# STM32G473QETx_LQFP128_MCU.net
KiCad netlist of a schematic drawn in Altium Designer
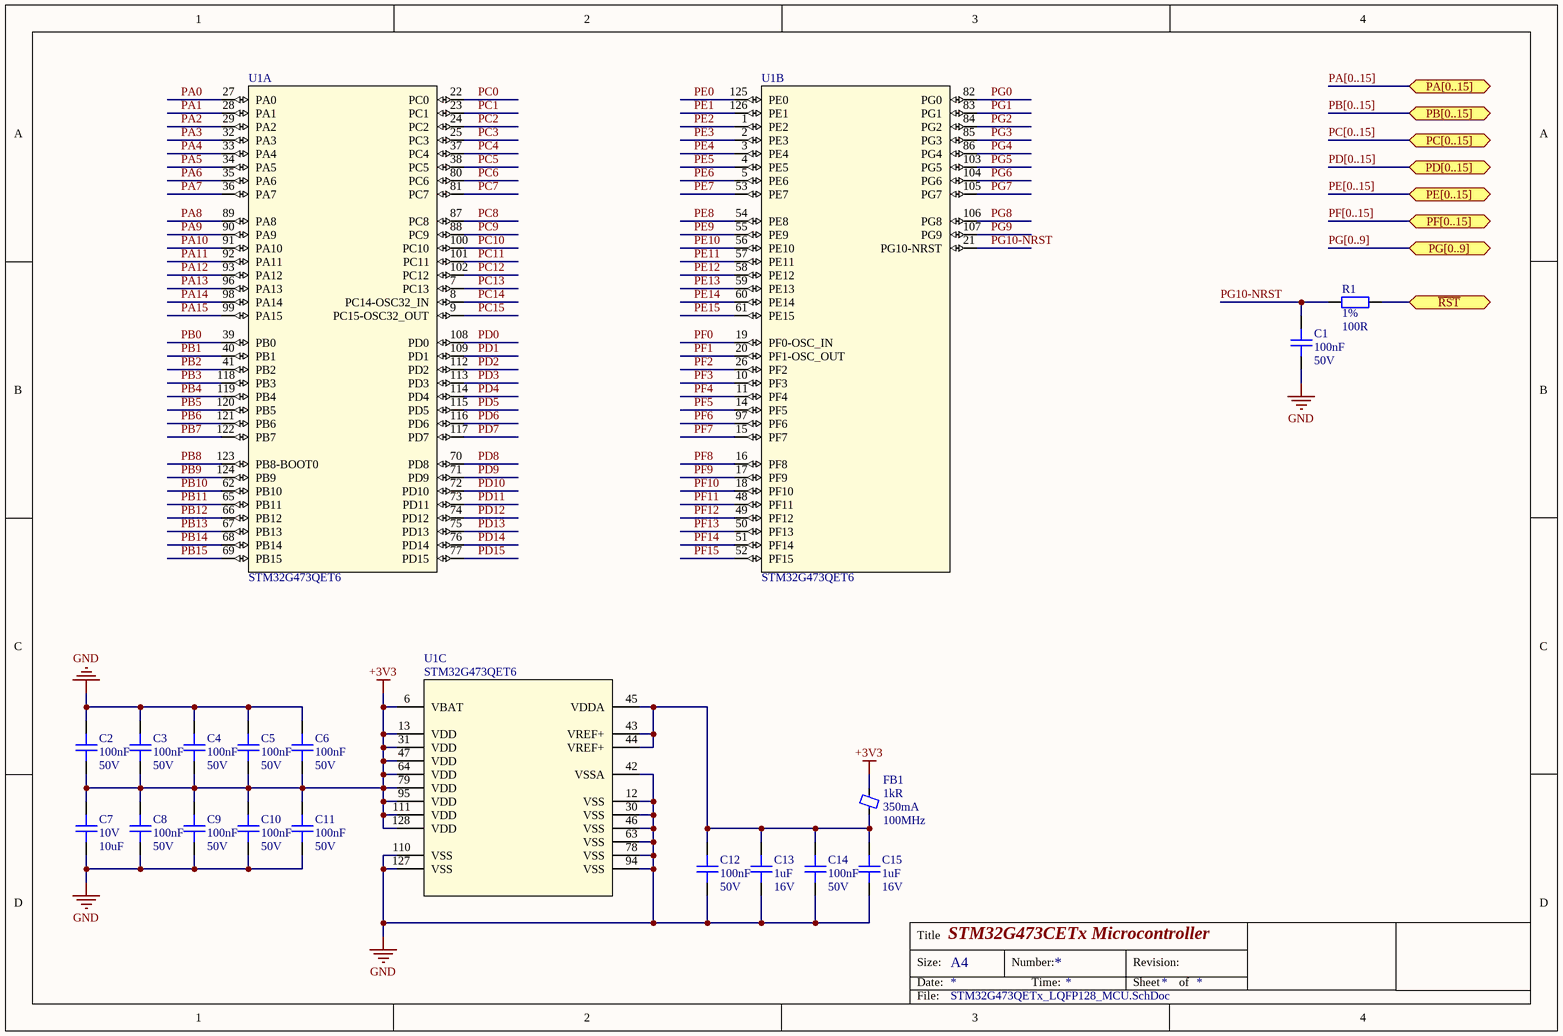
[diagram p0: STM32G473QETx_LQFP128_MCU.SchDoc]

(export (version "E")
  (design (tool "Eeschema 10.0.6"))
  (components
    (comp (ref "C1")
      (value "CAP CER 0.1UF 50V X7R 0402")
      (footprint "C0402")
      (description "0.1µF ±10% 50V Ceramic Capacitor X7R 0402 (1005 Metric)")
      (fields
        (field (name "MANUFACTURER") "TDK")
        (field (name "MANUFACTURER PART NUMBER") "CGA2B3X7R1H104K050BB")
        (field (name "CAPACITANCE") "100nF")
        (field (name "VOLTAGE") "50V")
      )
      (libsource (lib "capacitors_smd") (part "CAP CER 0.1UF 50V X7R 0402"))
    )
    (comp (ref "C2")
      (value "CAP CER 0.1UF 50V X7R 0402")
      (footprint "C0402")
      (description "0.1µF ±10% 50V Ceramic Capacitor X7R 0402 (1005 Metric)")
      (fields
        (field (name "MANUFACTURER") "TDK")
        (field (name "MANUFACTURER PART NUMBER") "CGA2B3X7R1H104K050BB")
        (field (name "CAPACITANCE") "100nF")
        (field (name "VOLTAGE") "50V")
      )
      (libsource (lib "capacitors_smd") (part "CAP CER 0.1UF 50V X7R 0402"))
    )
    (comp (ref "C3")
      (value "CAP CER 0.1UF 50V X7R 0402")
      (footprint "C0402")
      (description "0.1µF ±10% 50V Ceramic Capacitor X7R 0402 (1005 Metric)")
      (fields
        (field (name "MANUFACTURER") "TDK")
        (field (name "MANUFACTURER PART NUMBER") "CGA2B3X7R1H104K050BB")
        (field (name "CAPACITANCE") "100nF")
        (field (name "VOLTAGE") "50V")
      )
      (libsource (lib "capacitors_smd") (part "CAP CER 0.1UF 50V X7R 0402"))
    )
    (comp (ref "C4")
      (value "CAP CER 0.1UF 50V X7R 0402")
      (footprint "C0402")
      (description "0.1µF ±10% 50V Ceramic Capacitor X7R 0402 (1005 Metric)")
      (fields
        (field (name "MANUFACTURER") "TDK")
        (field (name "MANUFACTURER PART NUMBER") "CGA2B3X7R1H104K050BB")
        (field (name "CAPACITANCE") "100nF")
        (field (name "VOLTAGE") "50V")
      )
      (libsource (lib "capacitors_smd") (part "CAP CER 0.1UF 50V X7R 0402"))
    )
    (comp (ref "C5")
      (value "CAP CER 0.1UF 50V X7R 0402")
      (footprint "C0402")
      (description "0.1µF ±10% 50V Ceramic Capacitor X7R 0402 (1005 Metric)")
      (fields
        (field (name "MANUFACTURER") "TDK")
        (field (name "MANUFACTURER PART NUMBER") "CGA2B3X7R1H104K050BB")
        (field (name "CAPACITANCE") "100nF")
        (field (name "VOLTAGE") "50V")
      )
      (libsource (lib "capacitors_smd") (part "CAP CER 0.1UF 50V X7R 0402"))
    )
    (comp (ref "C6")
      (value "CAP CER 0.1UF 50V X7R 0402")
      (footprint "C0402")
      (description "0.1µF ±10% 50V Ceramic Capacitor X7R 0402 (1005 Metric)")
      (fields
        (field (name "MANUFACTURER") "TDK")
        (field (name "MANUFACTURER PART NUMBER") "CGA2B3X7R1H104K050BB")
        (field (name "CAPACITANCE") "100nF")
        (field (name "VOLTAGE") "50V")
      )
      (libsource (lib "capacitors_smd") (part "CAP CER 0.1UF 50V X7R 0402"))
    )
    (comp (ref "C7")
      (value "CAP CER 10uF X7R 10% 0805")
      (footprint "C0805")
      (description "Capacitor,10uF,10V,X7R,10%,0805,Murata")
      (fields
        (field (name "MANUFACTURER") "Murata")
        (field (name "MANUFACTURER PART NUMBER") "GRM21BR71A106KA73L")
        (field (name "VOLTAGE RATING") "10V")
        (field (name "CAPACITANCE") "10uF")
      )
      (libsource (lib "capacitors_smd") (part "CAP CER 10uF X7R 10% 0805"))
    )
    (comp (ref "C8")
      (value "CAP CER 0.1UF 50V X7R 0402")
      (footprint "C0402")
      (description "0.1µF ±10% 50V Ceramic Capacitor X7R 0402 (1005 Metric)")
      (fields
        (field (name "MANUFACTURER") "TDK")
        (field (name "MANUFACTURER PART NUMBER") "CGA2B3X7R1H104K050BB")
        (field (name "CAPACITANCE") "100nF")
        (field (name "VOLTAGE") "50V")
      )
      (libsource (lib "capacitors_smd") (part "CAP CER 0.1UF 50V X7R 0402"))
    )
    (comp (ref "C9")
      (value "CAP CER 0.1UF 50V X7R 0402")
      (footprint "C0402")
      (description "0.1µF ±10% 50V Ceramic Capacitor X7R 0402 (1005 Metric)")
      (fields
        (field (name "MANUFACTURER") "TDK")
        (field (name "MANUFACTURER PART NUMBER") "CGA2B3X7R1H104K050BB")
        (field (name "CAPACITANCE") "100nF")
        (field (name "VOLTAGE") "50V")
      )
      (libsource (lib "capacitors_smd") (part "CAP CER 0.1UF 50V X7R 0402"))
    )
    (comp (ref "C10")
      (value "CAP CER 0.1UF 50V X7R 0402")
      (footprint "C0402")
      (description "0.1µF ±10% 50V Ceramic Capacitor X7R 0402 (1005 Metric)")
      (fields
        (field (name "MANUFACTURER") "TDK")
        (field (name "MANUFACTURER PART NUMBER") "CGA2B3X7R1H104K050BB")
        (field (name "CAPACITANCE") "100nF")
        (field (name "VOLTAGE") "50V")
      )
      (libsource (lib "capacitors_smd") (part "CAP CER 0.1UF 50V X7R 0402"))
    )
    (comp (ref "C11")
      (value "CAP CER 0.1UF 50V X7R 0402")
      (footprint "C0402")
      (description "0.1µF ±10% 50V Ceramic Capacitor X7R 0402 (1005 Metric)")
      (fields
        (field (name "MANUFACTURER") "TDK")
        (field (name "MANUFACTURER PART NUMBER") "CGA2B3X7R1H104K050BB")
        (field (name "CAPACITANCE") "100nF")
        (field (name "VOLTAGE") "50V")
      )
      (libsource (lib "capacitors_smd") (part "CAP CER 0.1UF 50V X7R 0402"))
    )
    (comp (ref "C12")
      (value "CAP CER 0.1UF 50V X7R 0402")
      (footprint "C0402")
      (description "0.1µF ±10% 50V Ceramic Capacitor X7R 0402 (1005 Metric)")
      (fields
        (field (name "MANUFACTURER") "TDK")
        (field (name "MANUFACTURER PART NUMBER") "CGA2B3X7R1H104K050BB")
        (field (name "CAPACITANCE") "100nF")
        (field (name "VOLTAGE") "50V")
      )
      (libsource (lib "capacitors_smd") (part "CAP CER 0.1UF 50V X7R 0402"))
    )
    (comp (ref "C13")
      (value "CAP CER 1UF 16V X5R 0402")
      (footprint "C0402")
      (description "1µF ±10% 16V Ceramic Capacitor X5R 0402 (1005 Metric)")
      (fields
        (field (name "MANUFACTURER") "Yageo")
        (field (name "MANUFACTURER PART NUMBER") "CC0402KRX5R7BB105")
        (field (name "CAPACITANCE") "1uF")
        (field (name "VOLTAGE RATING") "16V")
      )
      (libsource (lib "capacitors_smd") (part "CAP CER 1UF 16V X5R 0402"))
    )
    (comp (ref "C14")
      (value "CAP CER 0.1UF 50V X7R 0402")
      (footprint "C0402")
      (description "0.1µF ±10% 50V Ceramic Capacitor X7R 0402 (1005 Metric)")
      (fields
        (field (name "MANUFACTURER") "TDK")
        (field (name "MANUFACTURER PART NUMBER") "CGA2B3X7R1H104K050BB")
        (field (name "CAPACITANCE") "100nF")
        (field (name "VOLTAGE") "50V")
      )
      (libsource (lib "capacitors_smd") (part "CAP CER 0.1UF 50V X7R 0402"))
    )
    (comp (ref "C15")
      (value "CAP CER 1UF 16V X5R 0402")
      (footprint "C0402")
      (description "1µF ±10% 16V Ceramic Capacitor X5R 0402 (1005 Metric)")
      (fields
        (field (name "MANUFACTURER") "Yageo")
        (field (name "MANUFACTURER PART NUMBER") "CC0402KRX5R7BB105")
        (field (name "CAPACITANCE") "1uF")
        (field (name "VOLTAGE RATING") "16V")
      )
      (libsource (lib "capacitors_smd") (part "CAP CER 1UF 16V X5R 0402"))
    )
    (comp (ref "FB1")
      (value "FERRITE BEAD 1 KOHM 0402 1LN")
      (footprint "L0402")
      (description "1 kOhms @ 100MHz 1  Ferrite Bead 0402 (1005 Metric) 350mA 490mOhm")
      (fields
        (field (name "MANUFACTURER") "Murata")
        (field (name "MANUFACTURER PART NUMBER") "BLM15AX102SN1D")
        (field (name "IMPEDANCE") "1kR")
        (field (name "MAX DC CURRENT") "350mA")
        (field (name "TEST FREQUENCY") "100MHz")
      )
      (libsource (lib "ferrite_beads") (part "FERRITE BEAD 1 KOHM 0402 1LN"))
    )
    (comp (ref "R1")
      (value "RES SMD 100 OHM 1% 1/16W 0402")
      (footprint "R0402")
      (description "100 Ohms ±1% 0.063W, 1/16W Chip Resistor 0402 (1005 Metric) Moisture Resistant Thick Film")
      (fields
        (field (name "MANUFACTURER") "Yageo")
        (field (name "MANUFACTURER PART NUMBER") "RC0402FR-07100RL")
        (field (name "TOLERANCE") "1%")
        (field (name "RESISTANCE") "100R")
      )
      (libsource (lib "resistors_smd") (part "RES SMD 100 OHM 1% 1/16W 0402"))
    )
    (comp (ref "U1")
      (value "STM32G473QET6")
      (footprint "LPQFP-128")
      (description "ARM® Cortex®-M4 STM32G4 Microcontroller IC 32-Bit 170MHz 512KB (512K x 8) FLASH 128-LQFP (14x14)")
      (fields (field (name "MANUFACTURER") "STMicroelectronics"))
      (libsource (lib "BLDC_Motor_Driver") (part "IC STM32G473QETx MCU 32BIT 512KB FLASH 128LQFP"))
    )
  )
  (nets
    (net (code "1") (name "+3V3") (class "Default")
      (node (ref "C10") (pin "1") (pinfunction "1_1") (pintype "passive"))
      (node (ref "C11") (pin "1") (pinfunction "1_1") (pintype "passive"))
      (node (ref "C2") (pin "2") (pinfunction "2_2") (pintype "passive"))
      (node (ref "C3") (pin "2") (pinfunction "2_2") (pintype "passive"))
      (node (ref "C4") (pin "2") (pinfunction "2_2") (pintype "passive"))
      (node (ref "C5") (pin "2") (pinfunction "2_2") (pintype "passive"))
      (node (ref "C6") (pin "1") (pinfunction "1_1") (pintype "passive"))
      (node (ref "C7") (pin "1") (pinfunction "1_1") (pintype "passive"))
      (node (ref "C8") (pin "1") (pinfunction "1_1") (pintype "passive"))
      (node (ref "C9") (pin "1") (pinfunction "1_1") (pintype "passive"))
      (node (ref "FB1") (pin "2") (pinfunction "2_2") (pintype "passive"))
      (node (ref "U1") (pin "111") (pinfunction "VDD_111") (pintype "power_in"))
      (node (ref "U1") (pin "128") (pinfunction "VDD_128") (pintype "power_in"))
      (node (ref "U1") (pin "13") (pinfunction "VDD_13") (pintype "power_in"))
      (node (ref "U1") (pin "31") (pinfunction "VDD_31") (pintype "power_in"))
      (node (ref "U1") (pin "47") (pinfunction "VDD_47") (pintype "power_in"))
      (node (ref "U1") (pin "6") (pinfunction "VBAT_6") (pintype "power_in"))
      (node (ref "U1") (pin "64") (pinfunction "VDD_64") (pintype "power_in"))
      (node (ref "U1") (pin "79") (pinfunction "VDD_79") (pintype "power_in"))
      (node (ref "U1") (pin "95") (pinfunction "VDD_95") (pintype "power_in"))
    )
    (net (code "2") (name "/PA0") (class "Default")
      (node (ref "U1") (pin "27") (pinfunction "PA0_27") (pintype "bidirectional"))
    )
    (net (code "3") (name "/PA1") (class "Default")
      (node (ref "U1") (pin "28") (pinfunction "PA1_28") (pintype "bidirectional"))
    )
    (net (code "4") (name "/PA2") (class "Default")
      (node (ref "U1") (pin "29") (pinfunction "PA2_29") (pintype "bidirectional"))
    )
    (net (code "5") (name "/PA3") (class "Default")
      (node (ref "U1") (pin "32") (pinfunction "PA3_32") (pintype "bidirectional"))
    )
    (net (code "6") (name "/PA4") (class "Default")
      (node (ref "U1") (pin "33") (pinfunction "PA4_33") (pintype "bidirectional"))
    )
    (net (code "7") (name "/PA5") (class "Default")
      (node (ref "U1") (pin "34") (pinfunction "PA5_34") (pintype "bidirectional"))
    )
    (net (code "8") (name "/PA6") (class "Default")
      (node (ref "U1") (pin "35") (pinfunction "PA6_35") (pintype "bidirectional"))
    )
    (net (code "9") (name "/PA7") (class "Default")
      (node (ref "U1") (pin "36") (pinfunction "PA7_36") (pintype "bidirectional"))
    )
    (net (code "10") (name "/PA8") (class "Default")
      (node (ref "U1") (pin "89") (pinfunction "PA8_89") (pintype "bidirectional"))
    )
    (net (code "11") (name "/PA9") (class "Default")
      (node (ref "U1") (pin "90") (pinfunction "PA9_90") (pintype "bidirectional"))
    )
    (net (code "12") (name "/PA10") (class "Default")
      (node (ref "U1") (pin "91") (pinfunction "PA10_91") (pintype "bidirectional"))
    )
    (net (code "13") (name "/PA11") (class "Default")
      (node (ref "U1") (pin "92") (pinfunction "PA11_92") (pintype "bidirectional"))
    )
    (net (code "14") (name "/PA12") (class "Default")
      (node (ref "U1") (pin "93") (pinfunction "PA12_93") (pintype "bidirectional"))
    )
    (net (code "15") (name "/PA13") (class "Default")
      (node (ref "U1") (pin "96") (pinfunction "PA13_96") (pintype "bidirectional"))
    )
    (net (code "16") (name "/PA14") (class "Default")
      (node (ref "U1") (pin "98") (pinfunction "PA14_98") (pintype "bidirectional"))
    )
    (net (code "17") (name "/PA15") (class "Default")
      (node (ref "U1") (pin "99") (pinfunction "PA15_99") (pintype "bidirectional"))
    )
    (net (code "19") (name "/PB0") (class "Default")
      (node (ref "U1") (pin "39") (pinfunction "PB0_39") (pintype "bidirectional"))
    )
    (net (code "20") (name "/PB1") (class "Default")
      (node (ref "U1") (pin "40") (pinfunction "PB1_40") (pintype "bidirectional"))
    )
    (net (code "21") (name "/PB2") (class "Default")
      (node (ref "U1") (pin "41") (pinfunction "PB2_41") (pintype "bidirectional"))
    )
    (net (code "22") (name "/PB3") (class "Default")
      (node (ref "U1") (pin "118") (pinfunction "PB3_118") (pintype "bidirectional"))
    )
    (net (code "23") (name "/PB4") (class "Default")
      (node (ref "U1") (pin "119") (pinfunction "PB4_119") (pintype "bidirectional"))
    )
    (net (code "24") (name "/PB5") (class "Default")
      (node (ref "U1") (pin "120") (pinfunction "PB5_120") (pintype "bidirectional"))
    )
    (net (code "25") (name "/PB6") (class "Default")
      (node (ref "U1") (pin "121") (pinfunction "PB6_121") (pintype "bidirectional"))
    )
    (net (code "26") (name "/PB7") (class "Default")
      (node (ref "U1") (pin "122") (pinfunction "PB7_122") (pintype "bidirectional"))
    )
    (net (code "27") (name "/PB8") (class "Default")
      (node (ref "U1") (pin "123") (pinfunction "PB8-BOOT0_123") (pintype "bidirectional"))
    )
    (net (code "28") (name "/PB9") (class "Default")
      (node (ref "U1") (pin "124") (pinfunction "PB9_124") (pintype "bidirectional"))
    )
    (net (code "29") (name "/PB10") (class "Default")
      (node (ref "U1") (pin "62") (pinfunction "PB10_62") (pintype "bidirectional"))
    )
    (net (code "30") (name "/PB11") (class "Default")
      (node (ref "U1") (pin "65") (pinfunction "PB11_65") (pintype "bidirectional"))
    )
    (net (code "31") (name "/PB12") (class "Default")
      (node (ref "U1") (pin "66") (pinfunction "PB12_66") (pintype "bidirectional"))
    )
    (net (code "32") (name "/PB13") (class "Default")
      (node (ref "U1") (pin "67") (pinfunction "PB13_67") (pintype "bidirectional"))
    )
    (net (code "33") (name "/PB14") (class "Default")
      (node (ref "U1") (pin "68") (pinfunction "PB14_68") (pintype "bidirectional"))
    )
    (net (code "34") (name "/PB15") (class "Default")
      (node (ref "U1") (pin "69") (pinfunction "PB15_69") (pintype "bidirectional"))
    )
    (net (code "36") (name "/PC0") (class "Default")
      (node (ref "U1") (pin "22") (pinfunction "PC0_22") (pintype "bidirectional"))
    )
    (net (code "37") (name "/PC1") (class "Default")
      (node (ref "U1") (pin "23") (pinfunction "PC1_23") (pintype "bidirectional"))
    )
    (net (code "38") (name "/PC2") (class "Default")
      (node (ref "U1") (pin "24") (pinfunction "PC2_24") (pintype "bidirectional"))
    )
    (net (code "39") (name "/PC3") (class "Default")
      (node (ref "U1") (pin "25") (pinfunction "PC3_25") (pintype "bidirectional"))
    )
    (net (code "40") (name "/PC4") (class "Default")
      (node (ref "U1") (pin "37") (pinfunction "PC4_37") (pintype "bidirectional"))
    )
    (net (code "41") (name "/PC5") (class "Default")
      (node (ref "U1") (pin "38") (pinfunction "PC5_38") (pintype "bidirectional"))
    )
    (net (code "42") (name "/PC6") (class "Default")
      (node (ref "U1") (pin "80") (pinfunction "PC6_80") (pintype "bidirectional"))
    )
    (net (code "43") (name "/PC7") (class "Default")
      (node (ref "U1") (pin "81") (pinfunction "PC7_81") (pintype "bidirectional"))
    )
    (net (code "44") (name "/PC8") (class "Default")
      (node (ref "U1") (pin "87") (pinfunction "PC8_87") (pintype "bidirectional"))
    )
    (net (code "45") (name "/PC9") (class "Default")
      (node (ref "U1") (pin "88") (pinfunction "PC9_88") (pintype "bidirectional"))
    )
    (net (code "46") (name "/PC10") (class "Default")
      (node (ref "U1") (pin "100") (pinfunction "PC10_100") (pintype "bidirectional"))
    )
    (net (code "47") (name "/PC11") (class "Default")
      (node (ref "U1") (pin "101") (pinfunction "PC11_101") (pintype "bidirectional"))
    )
    (net (code "48") (name "/PC12") (class "Default")
      (node (ref "U1") (pin "102") (pinfunction "PC12_102") (pintype "bidirectional"))
    )
    (net (code "49") (name "/PC13") (class "Default")
      (node (ref "U1") (pin "7") (pinfunction "PC13_7") (pintype "bidirectional"))
    )
    (net (code "50") (name "/PC14") (class "Default")
      (node (ref "U1") (pin "8") (pinfunction "PC14-OSC32_IN_8") (pintype "bidirectional"))
    )
    (net (code "51") (name "/PC15") (class "Default")
      (node (ref "U1") (pin "9") (pinfunction "PC15-OSC32_OUT_9") (pintype "bidirectional"))
    )
    (net (code "53") (name "/PD0") (class "Default")
      (node (ref "U1") (pin "108") (pinfunction "PD0_108") (pintype "bidirectional"))
    )
    (net (code "54") (name "/PD1") (class "Default")
      (node (ref "U1") (pin "109") (pinfunction "PD1_109") (pintype "bidirectional"))
    )
    (net (code "55") (name "/PD2") (class "Default")
      (node (ref "U1") (pin "112") (pinfunction "PD2_112") (pintype "bidirectional"))
    )
    (net (code "56") (name "/PD3") (class "Default")
      (node (ref "U1") (pin "113") (pinfunction "PD3_113") (pintype "bidirectional"))
    )
    (net (code "57") (name "/PD4") (class "Default")
      (node (ref "U1") (pin "114") (pinfunction "PD4_114") (pintype "bidirectional"))
    )
    (net (code "58") (name "/PD5") (class "Default")
      (node (ref "U1") (pin "115") (pinfunction "PD5_115") (pintype "bidirectional"))
    )
    (net (code "59") (name "/PD6") (class "Default")
      (node (ref "U1") (pin "116") (pinfunction "PD6_116") (pintype "bidirectional"))
    )
    (net (code "60") (name "/PD7") (class "Default")
      (node (ref "U1") (pin "117") (pinfunction "PD7_117") (pintype "bidirectional"))
    )
    (net (code "61") (name "/PD8") (class "Default")
      (node (ref "U1") (pin "70") (pinfunction "PD8_70") (pintype "bidirectional"))
    )
    (net (code "62") (name "/PD9") (class "Default")
      (node (ref "U1") (pin "71") (pinfunction "PD9_71") (pintype "bidirectional"))
    )
    (net (code "63") (name "/PD10") (class "Default")
      (node (ref "U1") (pin "72") (pinfunction "PD10_72") (pintype "bidirectional"))
    )
    (net (code "64") (name "/PD11") (class "Default")
      (node (ref "U1") (pin "73") (pinfunction "PD11_73") (pintype "bidirectional"))
    )
    (net (code "65") (name "/PD12") (class "Default")
      (node (ref "U1") (pin "74") (pinfunction "PD12_74") (pintype "bidirectional"))
    )
    (net (code "66") (name "/PD13") (class "Default")
      (node (ref "U1") (pin "75") (pinfunction "PD13_75") (pintype "bidirectional"))
    )
    (net (code "67") (name "/PD14") (class "Default")
      (node (ref "U1") (pin "76") (pinfunction "PD14_76") (pintype "bidirectional"))
    )
    (net (code "68") (name "/PD15") (class "Default")
      (node (ref "U1") (pin "77") (pinfunction "PD15_77") (pintype "bidirectional"))
    )
    (net (code "70") (name "/PE0") (class "Default")
      (node (ref "U1") (pin "125") (pinfunction "PE0_125") (pintype "bidirectional"))
    )
    (net (code "71") (name "/PE1") (class "Default")
      (node (ref "U1") (pin "126") (pinfunction "PE1_126") (pintype "bidirectional"))
    )
    (net (code "72") (name "/PE2") (class "Default")
      (node (ref "U1") (pin "1") (pinfunction "PE2_1") (pintype "bidirectional"))
    )
    (net (code "73") (name "/PE3") (class "Default")
      (node (ref "U1") (pin "2") (pinfunction "PE3_2") (pintype "bidirectional"))
    )
    (net (code "74") (name "/PE4") (class "Default")
      (node (ref "U1") (pin "3") (pinfunction "PE4_3") (pintype "bidirectional"))
    )
    (net (code "75") (name "/PE5") (class "Default")
      (node (ref "U1") (pin "4") (pinfunction "PE5_4") (pintype "bidirectional"))
    )
    (net (code "76") (name "/PE6") (class "Default")
      (node (ref "U1") (pin "5") (pinfunction "PE6_5") (pintype "bidirectional"))
    )
    (net (code "77") (name "/PE7") (class "Default")
      (node (ref "U1") (pin "53") (pinfunction "PE7_53") (pintype "bidirectional"))
    )
    (net (code "78") (name "/PE8") (class "Default")
      (node (ref "U1") (pin "54") (pinfunction "PE8_54") (pintype "bidirectional"))
    )
    (net (code "79") (name "/PE9") (class "Default")
      (node (ref "U1") (pin "55") (pinfunction "PE9_55") (pintype "bidirectional"))
    )
    (net (code "80") (name "/PE10") (class "Default")
      (node (ref "U1") (pin "56") (pinfunction "PE10_56") (pintype "bidirectional"))
    )
    (net (code "81") (name "/PE11") (class "Default")
      (node (ref "U1") (pin "57") (pinfunction "PE11_57") (pintype "bidirectional"))
    )
    (net (code "82") (name "/PE12") (class "Default")
      (node (ref "U1") (pin "58") (pinfunction "PE12_58") (pintype "bidirectional"))
    )
    (net (code "83") (name "/PE13") (class "Default")
      (node (ref "U1") (pin "59") (pinfunction "PE13_59") (pintype "bidirectional"))
    )
    (net (code "84") (name "/PE14") (class "Default")
      (node (ref "U1") (pin "60") (pinfunction "PE14_60") (pintype "bidirectional"))
    )
    (net (code "85") (name "/PE15") (class "Default")
      (node (ref "U1") (pin "61") (pinfunction "PE15_61") (pintype "bidirectional"))
    )
    (net (code "87") (name "/PF0") (class "Default")
      (node (ref "U1") (pin "19") (pinfunction "PF0-OSC_IN_19") (pintype "bidirectional"))
    )
    (net (code "88") (name "/PF1") (class "Default")
      (node (ref "U1") (pin "20") (pinfunction "PF1-OSC_OUT_20") (pintype "bidirectional"))
    )
    (net (code "89") (name "/PF2") (class "Default")
      (node (ref "U1") (pin "26") (pinfunction "PF2_26") (pintype "bidirectional"))
    )
    (net (code "90") (name "/PF3") (class "Default")
      (node (ref "U1") (pin "10") (pinfunction "PF3_10") (pintype "bidirectional"))
    )
    (net (code "91") (name "/PF4") (class "Default")
      (node (ref "U1") (pin "11") (pinfunction "PF4_11") (pintype "bidirectional"))
    )
    (net (code "92") (name "/PF5") (class "Default")
      (node (ref "U1") (pin "14") (pinfunction "PF5_14") (pintype "bidirectional"))
    )
    (net (code "93") (name "/PF6") (class "Default")
      (node (ref "U1") (pin "97") (pinfunction "PF6_97") (pintype "bidirectional"))
    )
    (net (code "94") (name "/PF7") (class "Default")
      (node (ref "U1") (pin "15") (pinfunction "PF7_15") (pintype "bidirectional"))
    )
    (net (code "95") (name "/PF8") (class "Default")
      (node (ref "U1") (pin "16") (pinfunction "PF8_16") (pintype "bidirectional"))
    )
    (net (code "96") (name "/PF9") (class "Default")
      (node (ref "U1") (pin "17") (pinfunction "PF9_17") (pintype "bidirectional"))
    )
    (net (code "97") (name "/PF10") (class "Default")
      (node (ref "U1") (pin "18") (pinfunction "PF10_18") (pintype "bidirectional"))
    )
    (net (code "98") (name "/PF11") (class "Default")
      (node (ref "U1") (pin "48") (pinfunction "PF11_48") (pintype "bidirectional"))
    )
    (net (code "99") (name "/PF12") (class "Default")
      (node (ref "U1") (pin "49") (pinfunction "PF12_49") (pintype "bidirectional"))
    )
    (net (code "100") (name "/PF13") (class "Default")
      (node (ref "U1") (pin "50") (pinfunction "PF13_50") (pintype "bidirectional"))
    )
    (net (code "101") (name "/PF14") (class "Default")
      (node (ref "U1") (pin "51") (pinfunction "PF14_51") (pintype "bidirectional"))
    )
    (net (code "102") (name "/PF15") (class "Default")
      (node (ref "U1") (pin "52") (pinfunction "PF15_52") (pintype "bidirectional"))
    )
    (net (code "104") (name "/PG0") (class "Default")
      (node (ref "U1") (pin "82") (pinfunction "PG0_82") (pintype "bidirectional"))
    )
    (net (code "105") (name "/PG1") (class "Default")
      (node (ref "U1") (pin "83") (pinfunction "PG1_83") (pintype "bidirectional"))
    )
    (net (code "106") (name "/PG2") (class "Default")
      (node (ref "U1") (pin "84") (pinfunction "PG2_84") (pintype "bidirectional"))
    )
    (net (code "107") (name "/PG3") (class "Default")
      (node (ref "U1") (pin "85") (pinfunction "PG3_85") (pintype "bidirectional"))
    )
    (net (code "108") (name "/PG4") (class "Default")
      (node (ref "U1") (pin "86") (pinfunction "PG4_86") (pintype "bidirectional"))
    )
    (net (code "109") (name "/PG5") (class "Default")
      (node (ref "U1") (pin "103") (pinfunction "PG5_103") (pintype "bidirectional"))
    )
    (net (code "110") (name "/PG6") (class "Default")
      (node (ref "U1") (pin "104") (pinfunction "PG6_104") (pintype "bidirectional"))
    )
    (net (code "111") (name "/PG7") (class "Default")
      (node (ref "U1") (pin "105") (pinfunction "PG7_105") (pintype "bidirectional"))
    )
    (net (code "112") (name "/PG8") (class "Default")
      (node (ref "U1") (pin "106") (pinfunction "PG8_106") (pintype "bidirectional"))
    )
    (net (code "113") (name "/PG9") (class "Default")
      (node (ref "U1") (pin "107") (pinfunction "PG9_107") (pintype "bidirectional"))
    )
    (net (code "114") (name "/PG10-NRST") (class "Default")
      (node (ref "C1") (pin "1") (pinfunction "1_1") (pintype "passive"))
      (node (ref "R1") (pin "2") (pinfunction "2_2") (pintype "passive"))
      (node (ref "U1") (pin "21") (pinfunction "PG10-NRST_21") (pintype "bidirectional"))
    )
    (net (code "116") (name "/RST") (class "Default")
      (node (ref "R1") (pin "1") (pinfunction "1_1") (pintype "passive"))
    )
    (net (code "117") (name "GND") (class "Default")
      (node (ref "C1") (pin "2") (pinfunction "2_2") (pintype "passive"))
      (node (ref "C10") (pin "2") (pinfunction "2_2") (pintype "passive"))
      (node (ref "C11") (pin "2") (pinfunction "2_2") (pintype "passive"))
      (node (ref "C12") (pin "1") (pinfunction "1_1") (pintype "passive"))
      (node (ref "C13") (pin "1") (pinfunction "1_1") (pintype "passive"))
      (node (ref "C14") (pin "1") (pinfunction "1_1") (pintype "passive"))
      (node (ref "C15") (pin "1") (pinfunction "1_1") (pintype "passive"))
      (node (ref "C2") (pin "1") (pinfunction "1_1") (pintype "passive"))
      (node (ref "C3") (pin "1") (pinfunction "1_1") (pintype "passive"))
      (node (ref "C4") (pin "1") (pinfunction "1_1") (pintype "passive"))
      (node (ref "C5") (pin "1") (pinfunction "1_1") (pintype "passive"))
      (node (ref "C6") (pin "2") (pinfunction "2_2") (pintype "passive"))
      (node (ref "C7") (pin "2") (pinfunction "2_2") (pintype "passive"))
      (node (ref "C8") (pin "2") (pinfunction "2_2") (pintype "passive"))
      (node (ref "C9") (pin "2") (pinfunction "2_2") (pintype "passive"))
      (node (ref "U1") (pin "110") (pinfunction "VSS_110") (pintype "power_in"))
      (node (ref "U1") (pin "12") (pinfunction "VSS_12") (pintype "power_in"))
      (node (ref "U1") (pin "127") (pinfunction "VSS_127") (pintype "power_in"))
      (node (ref "U1") (pin "30") (pinfunction "VSS_30") (pintype "power_in"))
      (node (ref "U1") (pin "42") (pinfunction "VSSA_42") (pintype "power_in"))
      (node (ref "U1") (pin "46") (pinfunction "VSS_46") (pintype "power_in"))
      (node (ref "U1") (pin "63") (pinfunction "VSS_63") (pintype "power_in"))
      (node (ref "U1") (pin "78") (pinfunction "VSS_78") (pintype "power_in"))
      (node (ref "U1") (pin "94") (pinfunction "VSS_94") (pintype "power_in"))
    )
    (net (code "118") (name "Net-(U1C-VDDA)") (class "Default")
      (node (ref "C12") (pin "2") (pinfunction "2_2") (pintype "passive"))
      (node (ref "C13") (pin "2") (pinfunction "2_2") (pintype "passive"))
      (node (ref "C14") (pin "2") (pinfunction "2_2") (pintype "passive"))
      (node (ref "C15") (pin "2") (pinfunction "2_2") (pintype "passive"))
      (node (ref "FB1") (pin "1") (pinfunction "1_1") (pintype "passive"))
      (node (ref "U1") (pin "43") (pinfunction "VREF+_43") (pintype "power_in"))
      (node (ref "U1") (pin "44") (pinfunction "VREF+_44") (pintype "power_in"))
      (node (ref "U1") (pin "45") (pinfunction "VDDA_45") (pintype "power_in"))
    )
  )
)
